# SCH_SMARTWATCH-pcb.net
KiCad netlist of a schematic drawn in EasyEDA
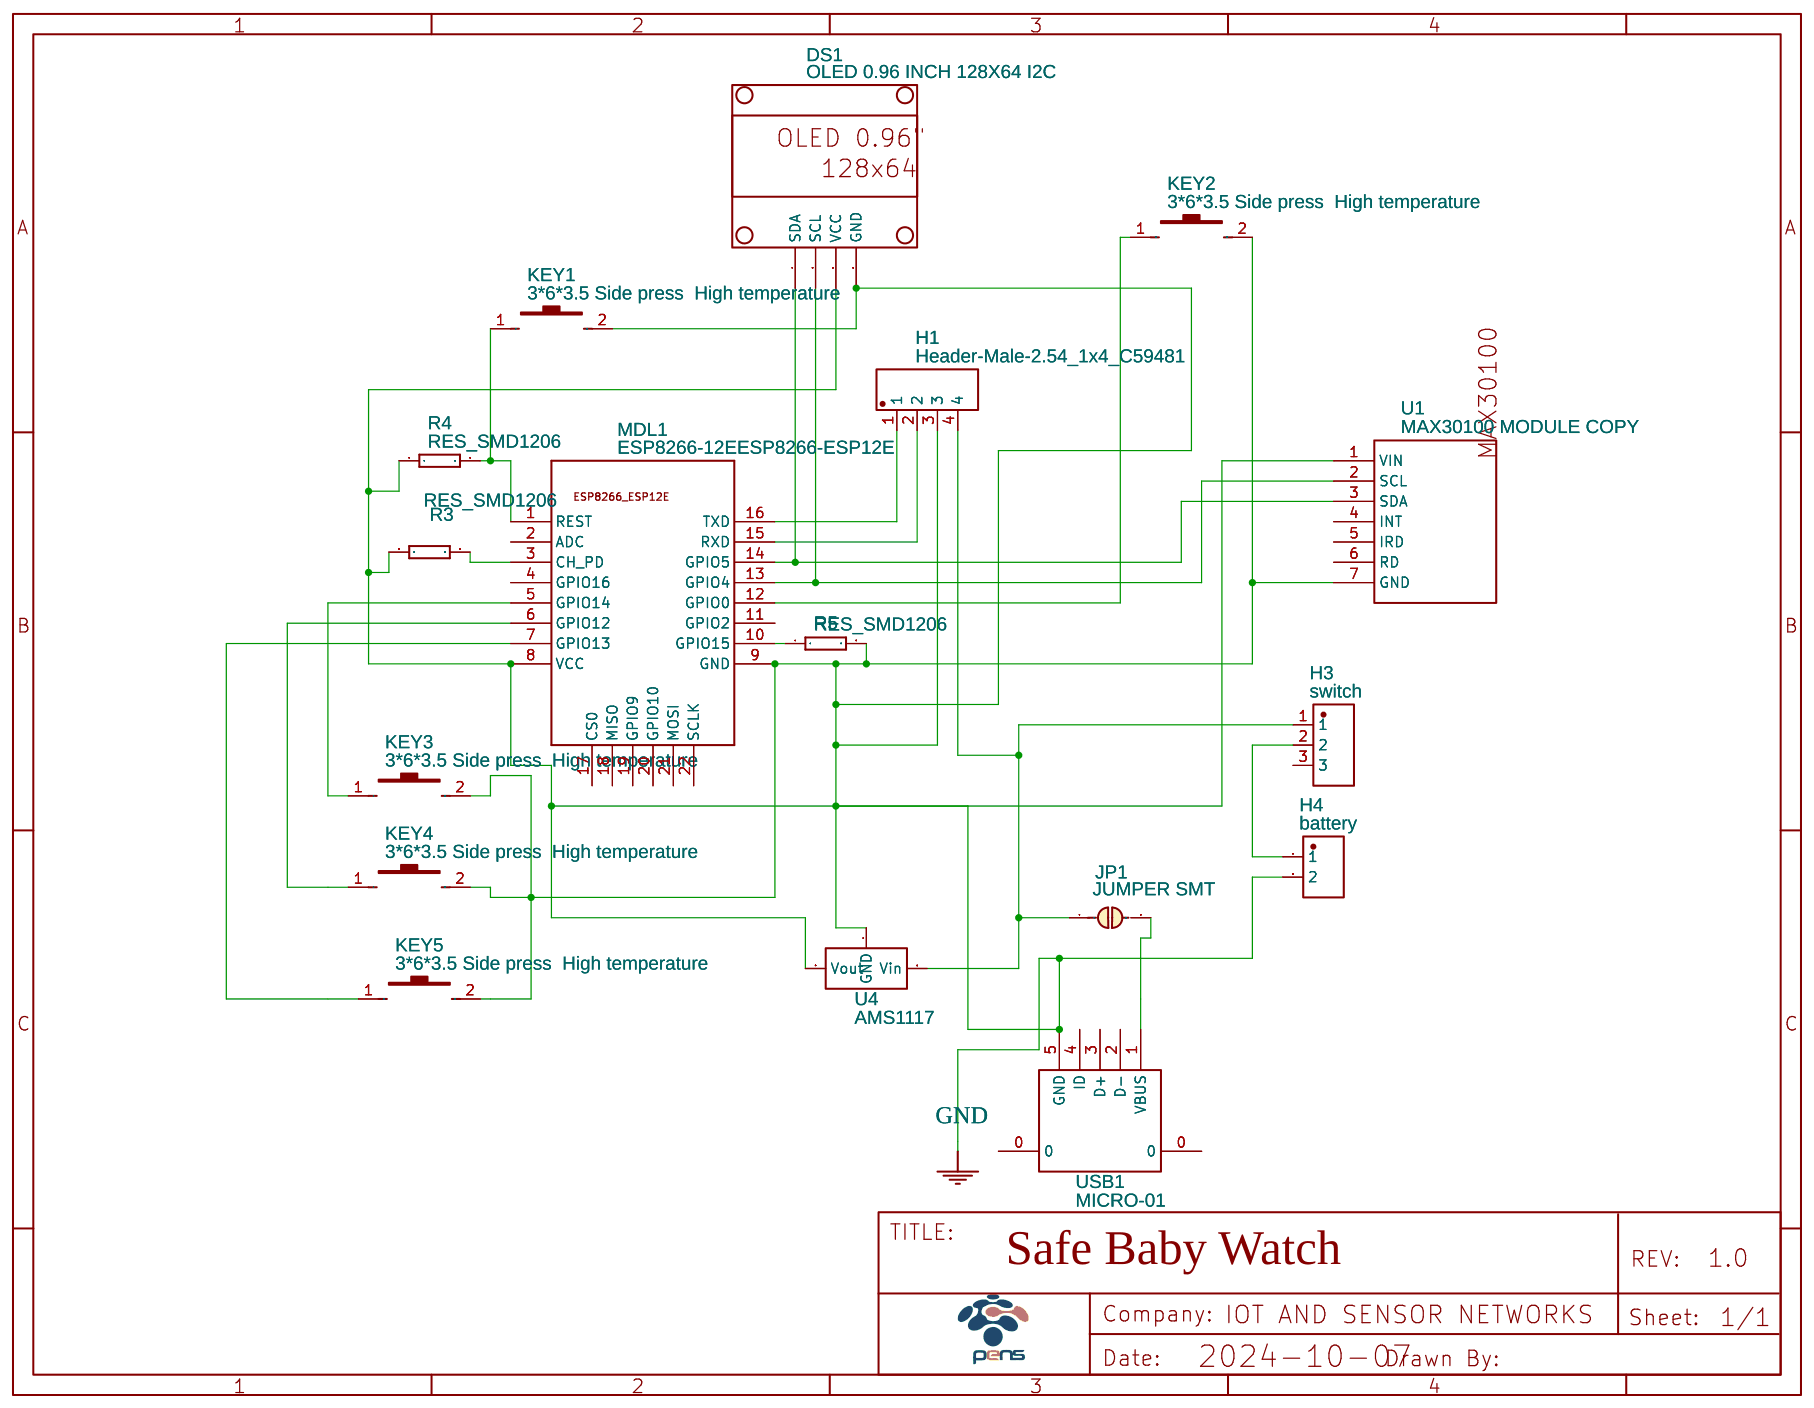
[diagram p0: schematic sheet]

(export (version "E")
  (design (tool "Eeschema 10.0.6"))
  (components
    (comp (ref "DS1")
      (value "OLED 0.96 INCH 128X64 I2C")
      (libsource (lib "") (part "OLED 0.96 INCH 128X64 I2C"))
    )
    (comp (ref "H1")
      (value "Header-Male-2.54_1x4_C59481")
      (fields
        (field (name "Manufacturer Part") "Headers  Pins 1*4P")
        (field (name "Manufacturer") "ReliaPro")
      )
      (libsource (lib "") (part "Header-Male-2.54_1x4_C59481"))
    )
    (comp (ref "H3")
      (value "switch")
      (fields
        (field (name "Manufacturer Part") "PZ254-1-03-Z-8.5")
        (field (name "Manufacturer") "HCTL(华灿天禄)")
      )
      (libsource (lib "") (part "PZ254-1-03-Z-8.5"))
    )
    (comp (ref "H4")
      (value "battery")
      (fields
        (field (name "Manufacturer Part") "MH254V-11-02-1000")
        (field (name "Manufacturer") "XFCN(台湾兴飞)")
      )
      (libsource (lib "") (part "MH254V-11-02-1000"))
    )
    (comp (ref "JP1") (value "JUMPER SMT") (libsource (lib "") (part "JUMPER SMT")))
    (comp (ref "KEY1")
      (value "3*6*3.5 Side press  High temperature")
      (fields (field (name "Manufacturer") "ReliaPro"))
      (libsource (lib "") (part "3*6*3.5 Side press  High temperature"))
    )
    (comp (ref "KEY2")
      (value "3*6*3.5 Side press  High temperature")
      (fields (field (name "Manufacturer") "ReliaPro"))
      (libsource (lib "") (part "3*6*3.5 Side press  High temperature"))
    )
    (comp (ref "KEY3")
      (value "3*6*3.5 Side press  High temperature")
      (fields (field (name "Manufacturer") "ReliaPro"))
      (libsource (lib "") (part "3*6*3.5 Side press  High temperature"))
    )
    (comp (ref "KEY4")
      (value "3*6*3.5 Side press  High temperature")
      (fields (field (name "Manufacturer") "ReliaPro"))
      (libsource (lib "") (part "3*6*3.5 Side press  High temperature"))
    )
    (comp (ref "KEY5")
      (value "3*6*3.5 Side press  High temperature")
      (fields (field (name "Manufacturer") "ReliaPro"))
      (libsource (lib "") (part "3*6*3.5 Side press  High temperature"))
    )
    (comp (ref "MDL1")
      (value "ESP8266-12EESP8266-ESP12E")
      (libsource (lib "") (part "ESP8266-12EESP8266-ESP12E"))
    )
    (comp (ref "R3")
      (value "RES_SMD1206")
      (fields (field (name "Manufacturer Part") "10K"))
      (libsource (lib "") (part "RES_SMD1206"))
    )
    (comp (ref "R4")
      (value "RES_SMD1206")
      (fields (field (name "Manufacturer Part") "10K"))
      (libsource (lib "") (part "RES_SMD1206"))
    )
    (comp (ref "R5")
      (value "RES_SMD1206")
      (fields (field (name "Manufacturer Part") "10K"))
      (libsource (lib "") (part "RES_SMD1206"))
    )
    (comp (ref "U1") (value "MAX30100 MODULE COPY") (libsource (lib "") (part "MAX30100 MODULE COPY")))
    (comp (ref "U4") (value "AMS1117") (libsource (lib "") (part "AMS1117")))
    (comp (ref "USB1")
      (value "MICRO-01")
      (fields (field (name "Manufacturer Part") "Micro-01") (field (name "Manufacturer") "SOFNG"))
      (libsource (lib "") (part "MICRO-01"))
    )
  )
  (nets
    (net (code "1") (name "GND") (class "Default")
      (node (ref "DS1") (pin "1") (pinfunction "GND_1") (pintype "unspecified"))
      (node (ref "DS1") (pin "2") (pinfunction "VCC_2") (pintype "unspecified"))
      (node (ref "H1") (pin "3") (pinfunction "3_3") (pintype "unspecified"))
      (node (ref "H4") (pin "2") (pinfunction "2_2") (pintype "unspecified"))
      (node (ref "KEY1") (pin "2") (pinfunction "2_2") (pintype "input"))
      (node (ref "KEY2") (pin "2") (pinfunction "2_2") (pintype "input"))
      (node (ref "KEY3") (pin "2") (pinfunction "2_2") (pintype "input"))
      (node (ref "KEY4") (pin "2") (pinfunction "2_2") (pintype "input"))
      (node (ref "KEY5") (pin "2") (pinfunction "2_2") (pintype "input"))
      (node (ref "MDL1") (pin "8") (pinfunction "VCC_8") (pintype "bidirectional"))
      (node (ref "MDL1") (pin "9") (pinfunction "GND_9") (pintype "bidirectional"))
      (node (ref "R3") (pin "1") (pinfunction "1_1") (pintype "unspecified"))
      (node (ref "R4") (pin "1") (pinfunction "1_1") (pintype "unspecified"))
      (node (ref "R5") (pin "2") (pinfunction "2_2") (pintype "unspecified"))
      (node (ref "U1") (pin "1") (pinfunction "VIN_1") (pintype "unspecified"))
      (node (ref "U1") (pin "7") (pinfunction "GND_7") (pintype "unspecified"))
      (node (ref "U4") (pin "1") (pinfunction "GND_1") (pintype "unspecified"))
      (node (ref "U4") (pin "2") (pinfunction "Vout_2") (pintype "unspecified"))
      (node (ref "USB1") (pin "5") (pinfunction "GND_5") (pintype "unspecified"))
    )
    (net (code "2") (name "Net-(DS1-SCL)") (class "Default")
      (node (ref "DS1") (pin "3") (pinfunction "SCL_3") (pintype "unspecified"))
      (node (ref "MDL1") (pin "13") (pinfunction "GPIO4_13") (pintype "bidirectional"))
      (node (ref "U1") (pin "2") (pinfunction "SCL_2") (pintype "unspecified"))
    )
    (net (code "3") (name "Net-(DS1-SDA)") (class "Default")
      (node (ref "DS1") (pin "4") (pinfunction "SDA_4") (pintype "unspecified"))
      (node (ref "MDL1") (pin "14") (pinfunction "GPIO5_14") (pintype "bidirectional"))
      (node (ref "U1") (pin "3") (pinfunction "SDA_3") (pintype "unspecified"))
    )
    (net (code "4") (name "Net-(H3-Pad2)") (class "Default")
      (node (ref "H3") (pin "2") (pinfunction "2_2") (pintype "unspecified"))
      (node (ref "H4") (pin "1") (pinfunction "1_1") (pintype "unspecified"))
    )
    (net (code "5") (name "Net-(MDL1-CH_PD)") (class "Default")
      (node (ref "MDL1") (pin "3") (pinfunction "CH_PD_3") (pintype "bidirectional"))
      (node (ref "R3") (pin "2") (pinfunction "2_2") (pintype "unspecified"))
    )
    (net (code "6") (name "Net-(MDL1-GPIO0)") (class "Default")
      (node (ref "KEY2") (pin "1") (pinfunction "1_1") (pintype "input"))
      (node (ref "MDL1") (pin "12") (pinfunction "GPIO0_12") (pintype "bidirectional"))
    )
    (net (code "7") (name "Net-(MDL1-GPIO12)") (class "Default")
      (node (ref "KEY4") (pin "1") (pinfunction "1_1") (pintype "input"))
      (node (ref "MDL1") (pin "6") (pinfunction "GPIO12_6") (pintype "bidirectional"))
    )
    (net (code "8") (name "Net-(MDL1-GPIO13)") (class "Default")
      (node (ref "KEY5") (pin "1") (pinfunction "1_1") (pintype "input"))
      (node (ref "MDL1") (pin "7") (pinfunction "GPIO13_7") (pintype "bidirectional"))
    )
    (net (code "9") (name "Net-(MDL1-GPIO14)") (class "Default")
      (node (ref "KEY3") (pin "1") (pinfunction "1_1") (pintype "input"))
      (node (ref "MDL1") (pin "5") (pinfunction "GPIO14_5") (pintype "bidirectional"))
    )
    (net (code "10") (name "Net-(MDL1-GPIO15)") (class "Default")
      (node (ref "MDL1") (pin "10") (pinfunction "GPIO15_10") (pintype "bidirectional"))
      (node (ref "R5") (pin "1") (pinfunction "1_1") (pintype "unspecified"))
    )
    (net (code "11") (name "Net-(MDL1-REST)") (class "Default")
      (node (ref "KEY1") (pin "1") (pinfunction "1_1") (pintype "input"))
      (node (ref "MDL1") (pin "1") (pinfunction "REST_1") (pintype "bidirectional"))
      (node (ref "R4") (pin "2") (pinfunction "2_2") (pintype "unspecified"))
    )
    (net (code "12") (name "Net-(MDL1-RXD)") (class "Default")
      (node (ref "H1") (pin "2") (pinfunction "2_2") (pintype "unspecified"))
      (node (ref "MDL1") (pin "15") (pinfunction "RXD_15") (pintype "bidirectional"))
    )
    (net (code "13") (name "Net-(MDL1-TXD)") (class "Default")
      (node (ref "H1") (pin "1") (pinfunction "1_1") (pintype "unspecified"))
      (node (ref "MDL1") (pin "16") (pinfunction "TXD_16") (pintype "bidirectional"))
    )
    (net (code "14") (name "Net-(U4-Vin)") (class "Default")
      (node (ref "H1") (pin "4") (pinfunction "4_4") (pintype "unspecified"))
      (node (ref "H3") (pin "1") (pinfunction "1_1") (pintype "unspecified"))
      (node (ref "JP1") (pin "1") (pinfunction "1_1") (pintype "bidirectional"))
      (node (ref "U4") (pin "3") (pinfunction "Vin_3") (pintype "unspecified"))
    )
    (net (code "15") (name "Net-(USB1-VBUS)") (class "Default")
      (node (ref "JP1") (pin "2") (pinfunction "2_2") (pintype "bidirectional"))
      (node (ref "USB1") (pin "1") (pinfunction "VBUS_1") (pintype "unspecified"))
    )
    (net (code "16") (name "unconnected-(H3-Pad3)") (class "Default")
      (node (ref "H3") (pin "3") (pinfunction "3_3") (pintype "unspecified"))
    )
    (net (code "17") (name "unconnected-(MDL1-ADC-Pad2)") (class "Default")
      (node (ref "MDL1") (pin "2") (pinfunction "ADC_2") (pintype "bidirectional"))
    )
    (net (code "18") (name "unconnected-(MDL1-CS0-Pad17)") (class "Default")
      (node (ref "MDL1") (pin "17") (pinfunction "CS0_17") (pintype "bidirectional"))
    )
    (net (code "19") (name "unconnected-(MDL1-GPIO2-Pad11)") (class "Default")
      (node (ref "MDL1") (pin "11") (pinfunction "GPIO2_11") (pintype "bidirectional"))
    )
    (net (code "20") (name "unconnected-(MDL1-GPIO9-Pad19)") (class "Default")
      (node (ref "MDL1") (pin "19") (pinfunction "GPIO9_19") (pintype "bidirectional"))
    )
    (net (code "21") (name "unconnected-(MDL1-GPIO10-Pad20)") (class "Default")
      (node (ref "MDL1") (pin "20") (pinfunction "GPIO10_20") (pintype "bidirectional"))
    )
    (net (code "22") (name "unconnected-(MDL1-GPIO16-Pad4)") (class "Default")
      (node (ref "MDL1") (pin "4") (pinfunction "GPIO16_4") (pintype "bidirectional"))
    )
    (net (code "23") (name "unconnected-(MDL1-MISO-Pad18)") (class "Default")
      (node (ref "MDL1") (pin "18") (pinfunction "MISO_18") (pintype "bidirectional"))
    )
    (net (code "24") (name "unconnected-(MDL1-MOSI-Pad21)") (class "Default")
      (node (ref "MDL1") (pin "21") (pinfunction "MOSI_21") (pintype "bidirectional"))
    )
    (net (code "25") (name "unconnected-(MDL1-SCLK-Pad22)") (class "Default")
      (node (ref "MDL1") (pin "22") (pinfunction "SCLK_22") (pintype "bidirectional"))
    )
    (net (code "26") (name "unconnected-(U1-INT-Pad4)") (class "Default")
      (node (ref "U1") (pin "4") (pinfunction "INT_4") (pintype "unspecified"))
    )
    (net (code "27") (name "unconnected-(U1-IRD-Pad5)") (class "Default")
      (node (ref "U1") (pin "5") (pinfunction "IRD_5") (pintype "unspecified"))
    )
    (net (code "28") (name "unconnected-(U1-RD-Pad6)") (class "Default")
      (node (ref "U1") (pin "6") (pinfunction "RD_6") (pintype "unspecified"))
    )
    (net (code "29") (name "unconnected-(USB1-D+-Pad3)") (class "Default")
      (node (ref "USB1") (pin "3") (pinfunction "D+_3") (pintype "unspecified"))
    )
    (net (code "30") (name "unconnected-(USB1-D--Pad2)") (class "Default")
      (node (ref "USB1") (pin "2") (pinfunction "D-_2") (pintype "unspecified"))
    )
    (net (code "31") (name "unconnected-(USB1-ID-Pad4)") (class "Default")
      (node (ref "USB1") (pin "4") (pinfunction "ID_4") (pintype "unspecified"))
    )
    (net (code "32") (name "unconnected-(USB1-Pad0)") (class "Default")
      (node (ref "USB1") (pin "0") (pinfunction "0_0") (pintype "unspecified"))
    )
    (net (code "33") (name "unconnected-(USB1-Pad0)_1") (class "Default")
      (node (ref "USB1") (pin "0") (pinfunction "0_0") (pintype "unspecified"))
    )
  )
)
